# pc.net
KiCad netlist of a schematic drawn in EAGLE
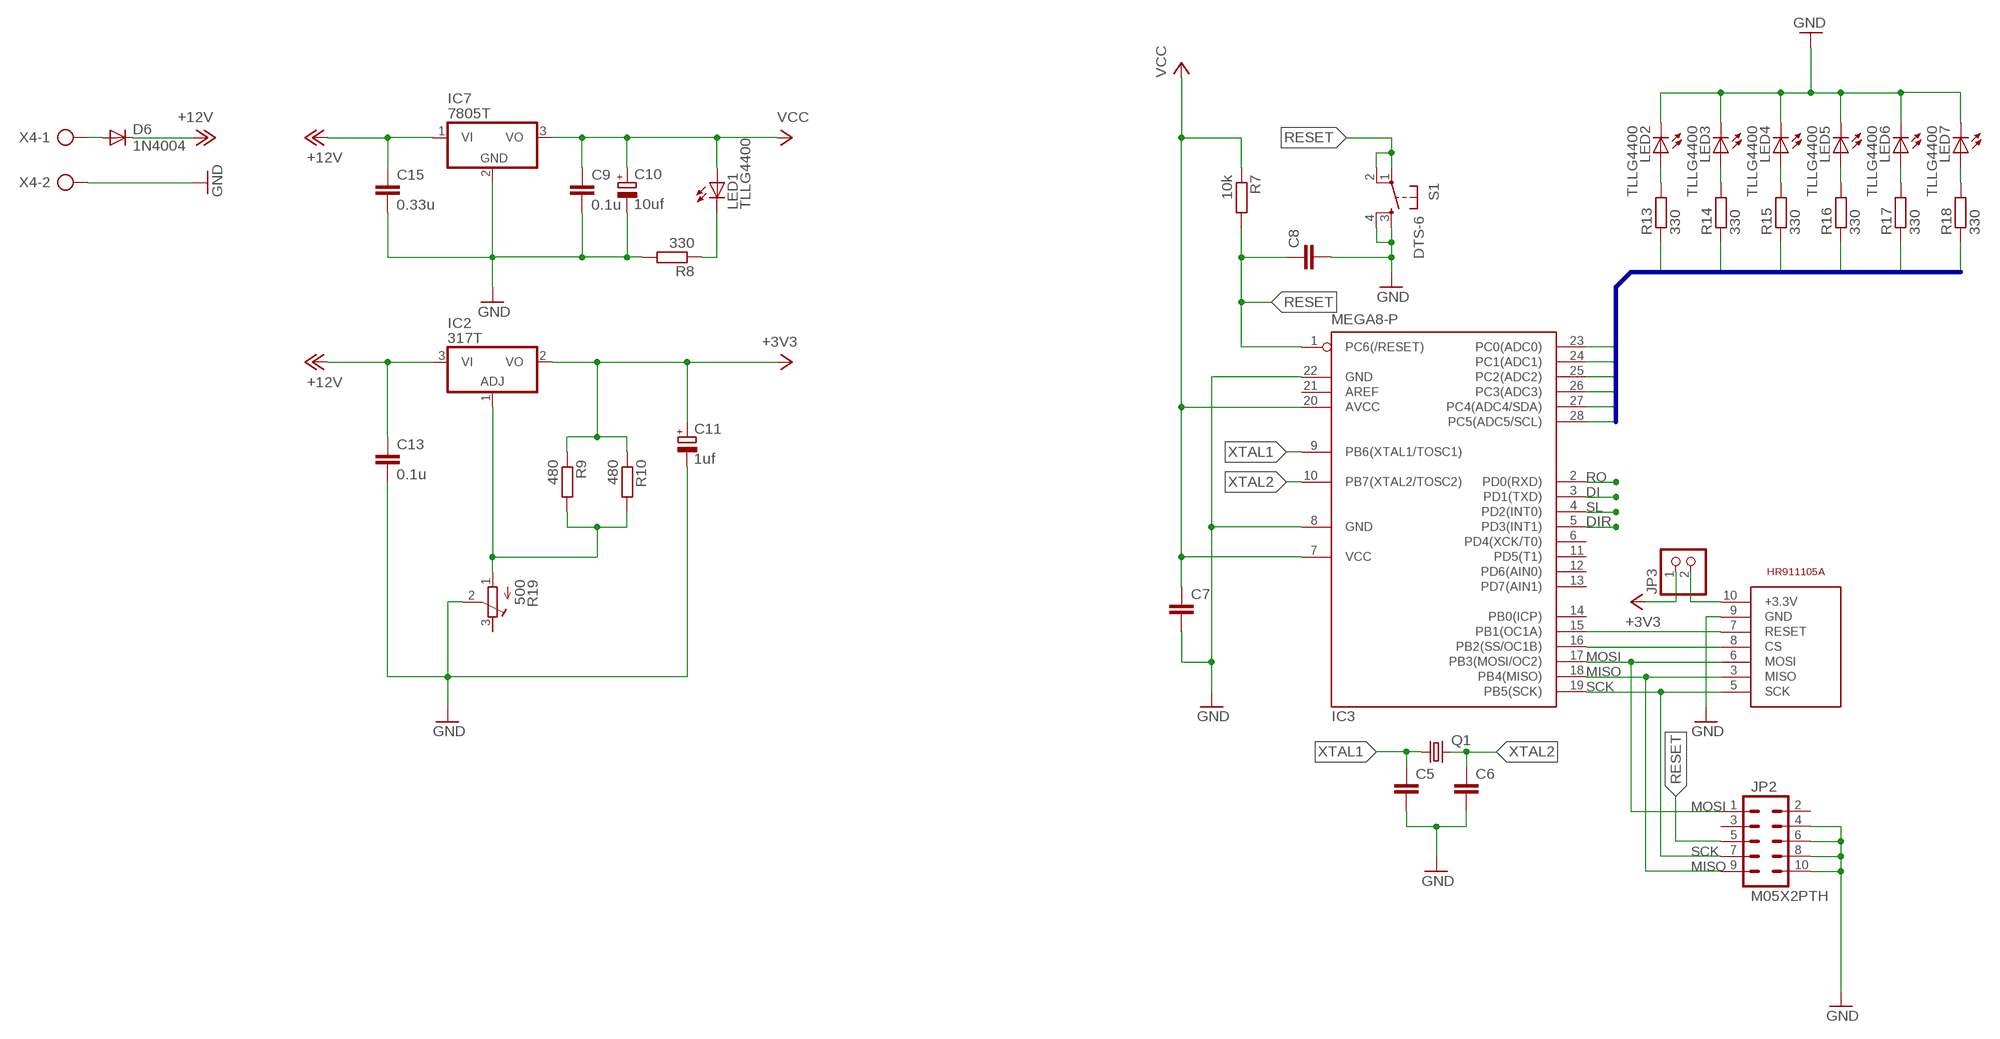
[diagram p0: schematic, sheet 1, part 1 of 2]
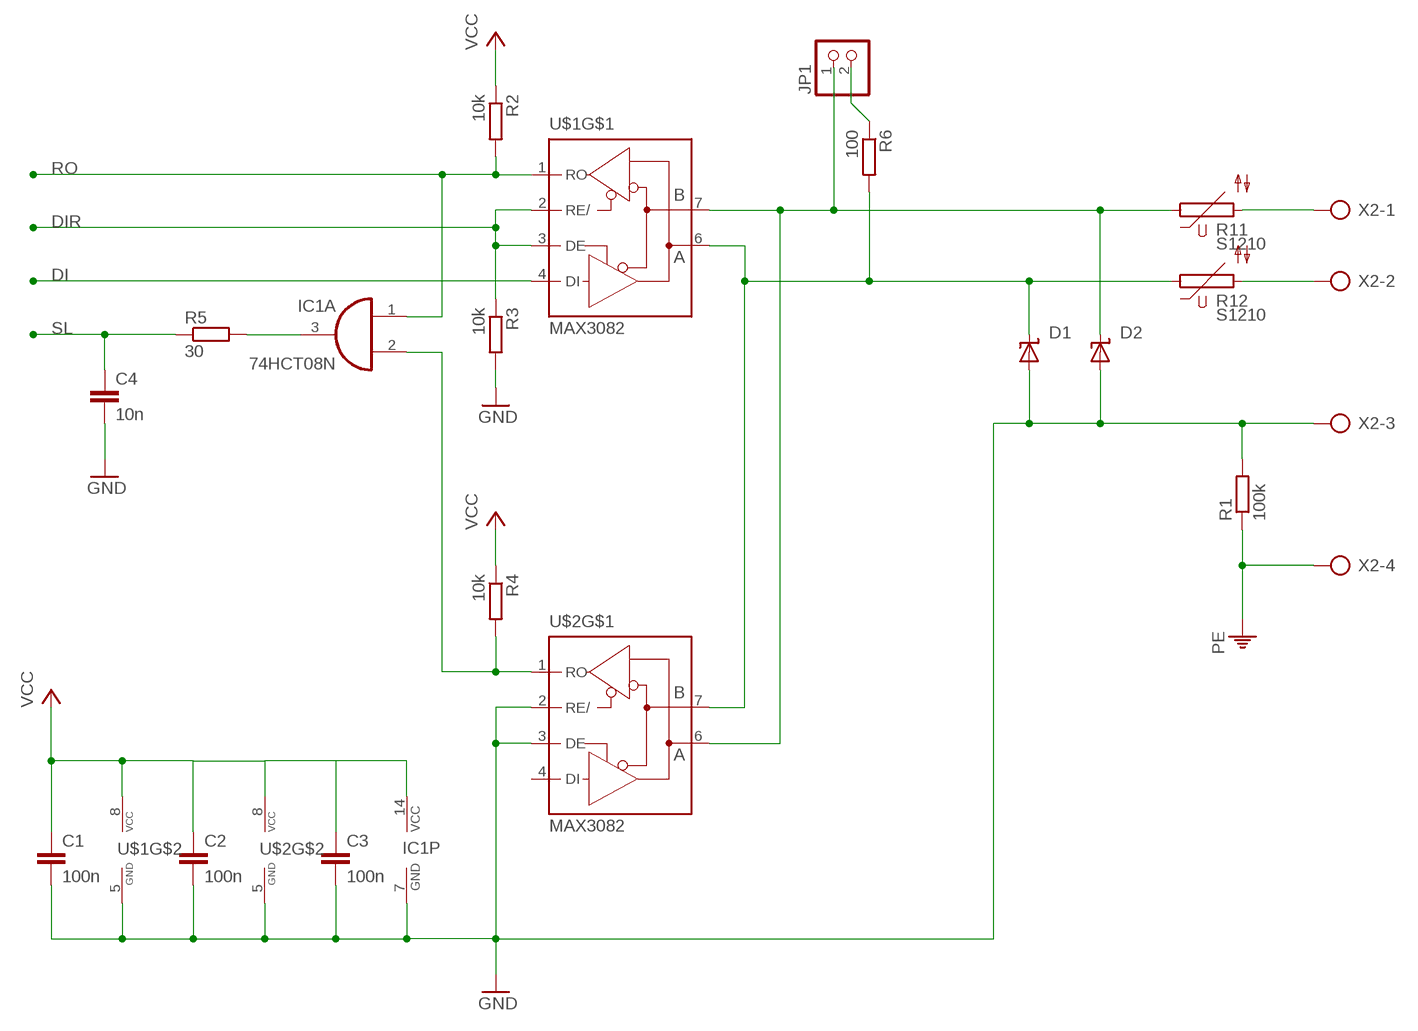
[diagram p1: schematic, sheet 1, part 2 of 2]

(export (version "E")
  (design (tool "Eeschema 10.0.6"))
  (components
    (comp (ref "C1")
      (value "100n")
      (footprint "eagle-import:C050-035X075")
      (libsource (lib "eagle-import") (part "C-EU050-035X075"))
    )
    (comp (ref "C2")
      (value "100n")
      (footprint "eagle-import:C050-035X075")
      (libsource (lib "eagle-import") (part "C-EU050-035X075"))
    )
    (comp (ref "C3")
      (value "100n")
      (footprint "eagle-import:C050-035X075")
      (libsource (lib "eagle-import") (part "C-EU050-035X075"))
    )
    (comp (ref "C4")
      (value "10n")
      (footprint "eagle-import:C050-035X075")
      (libsource (lib "eagle-import") (part "C-EU050-035X075"))
    )
    (comp (ref "C5")
      (value "C-EU050-024X044")
      (footprint "eagle-import:C050-024X044")
      (libsource (lib "eagle-import") (part "C-EU050-024X044"))
    )
    (comp (ref "C6")
      (value "C-EU050-024X044")
      (footprint "eagle-import:C050-024X044")
      (libsource (lib "eagle-import") (part "C-EU050-024X044"))
    )
    (comp (ref "C7")
      (value "C-EU050-025X075")
      (footprint "eagle-import:C050-025X075")
      (libsource (lib "eagle-import") (part "C-EU050-025X075"))
    )
    (comp (ref "C8")
      (value "C-EU050-025X075")
      (footprint "eagle-import:C050-025X075")
      (libsource (lib "eagle-import") (part "C-EU050-025X075"))
    )
    (comp (ref "C9")
      (value "0.1u")
      (footprint "eagle-import:C025-024X044")
      (libsource (lib "eagle-import") (part "C-EU025-024X044"))
    )
    (comp (ref "C10")
      (value "10uf")
      (footprint "eagle-import:E2-4")
      (libsource (lib "eagle-import") (part "CPOL-EUE2-4"))
    )
    (comp (ref "C11")
      (value "1uf")
      (footprint "eagle-import:E2-4")
      (libsource (lib "eagle-import") (part "CPOL-EUE2-4"))
    )
    (comp (ref "C13")
      (value "0.1u")
      (footprint "eagle-import:C025-024X044")
      (libsource (lib "eagle-import") (part "C-EU025-024X044"))
    )
    (comp (ref "C15")
      (value "0.33u")
      (footprint "eagle-import:C025-024X044")
      (libsource (lib "eagle-import") (part "C-EU025-024X044"))
    )
    (comp (ref "D1")
      (value "SUPPRESSOR-SMBJ")
      (footprint "eagle-import:SMBJ")
      (libsource (lib "eagle-import") (part "SUPPRESSOR-SMBJ"))
    )
    (comp (ref "D2")
      (value "SUPPRESSOR-SMBJ")
      (footprint "eagle-import:SMBJ")
      (libsource (lib "eagle-import") (part "SUPPRESSOR-SMBJ"))
    )
    (comp (ref "D6")
      (value "1N4004")
      (footprint "eagle-import:DO41-10")
      (libsource (lib "eagle-import") (part "1N4004"))
    )
    (comp (ref "IC1")
      (value "74HCT08N")
      (footprint "eagle-import:DIL14")
      (libsource (lib "eagle-import") (part "7408NHCT"))
    )
    (comp (ref "IC2")
      (value "317T")
      (footprint "eagle-import:TO220H")
      (libsource (lib "eagle-import") (part "317T"))
    )
    (comp (ref "IC3")
      (value "MEGA8-P")
      (footprint "eagle-import:DIL28-3")
      (libsource (lib "eagle-import") (part "MEGA8-P"))
    )
    (comp (ref "IC7")
      (value "7805T")
      (footprint "eagle-import:TO220H")
      (libsource (lib "eagle-import") (part "78T05"))
    )
    (comp (ref "JP1")
      (value "PINHD-1X2")
      (footprint "eagle-import:1X02")
      (libsource (lib "eagle-import") (part "PINHD-1X2"))
    )
    (comp (ref "JP2")
      (value "M05X2PTH")
      (footprint "eagle-import:AVR_ICSP")
      (libsource (lib "eagle-import") (part "M05X2PTH"))
    )
    (comp (ref "JP3")
      (value "PINHD-1X2")
      (footprint "eagle-import:1X02")
      (libsource (lib "eagle-import") (part "PINHD-1X2"))
    )
    (comp (ref "LED1")
      (value "TLLG4400")
      (footprint "eagle-import:LED3MM")
      (fields (field (name "MF") "VISHAY SEMICONDUCTOR"))
      (libsource (lib "eagle-import") (part "TLLG4400"))
    )
    (comp (ref "LED2")
      (value "TLLG4400")
      (footprint "eagle-import:LED3MM")
      (fields (field (name "MF") "VISHAY SEMICONDUCTOR"))
      (libsource (lib "eagle-import") (part "TLLG4400"))
    )
    (comp (ref "LED3")
      (value "TLLG4400")
      (footprint "eagle-import:LED3MM")
      (fields (field (name "MF") "VISHAY SEMICONDUCTOR"))
      (libsource (lib "eagle-import") (part "TLLG4400"))
    )
    (comp (ref "LED4")
      (value "TLLG4400")
      (footprint "eagle-import:LED3MM")
      (fields (field (name "MF") "VISHAY SEMICONDUCTOR"))
      (libsource (lib "eagle-import") (part "TLLG4400"))
    )
    (comp (ref "LED5")
      (value "TLLG4400")
      (footprint "eagle-import:LED3MM")
      (fields (field (name "MF") "VISHAY SEMICONDUCTOR"))
      (libsource (lib "eagle-import") (part "TLLG4400"))
    )
    (comp (ref "LED6")
      (value "TLLG4400")
      (footprint "eagle-import:LED3MM")
      (fields (field (name "MF") "VISHAY SEMICONDUCTOR"))
      (libsource (lib "eagle-import") (part "TLLG4400"))
    )
    (comp (ref "LED7")
      (value "TLLG4400")
      (footprint "eagle-import:LED3MM")
      (fields (field (name "MF") "VISHAY SEMICONDUCTOR"))
      (libsource (lib "eagle-import") (part "TLLG4400"))
    )
    (comp (ref "Q1")
      (value "CRYSTALHC49U70")
      (footprint "eagle-import:HC49U70")
      (libsource (lib "eagle-import") (part "CRYSTALHC49U70"))
    )
    (comp (ref "R1")
      (value "100k")
      (footprint "eagle-import:0204_7")
      (libsource (lib "eagle-import") (part "resistor_R-EU_0204/7"))
    )
    (comp (ref "R2")
      (value "10k")
      (footprint "eagle-import:0204_7")
      (libsource (lib "eagle-import") (part "resistor_R-EU_0204/7"))
    )
    (comp (ref "R3")
      (value "10k")
      (footprint "eagle-import:0204_7")
      (libsource (lib "eagle-import") (part "resistor_R-EU_0204/7"))
    )
    (comp (ref "R4")
      (value "10k")
      (footprint "eagle-import:0204_7")
      (libsource (lib "eagle-import") (part "resistor_R-EU_0204/7"))
    )
    (comp (ref "R5")
      (value "30")
      (footprint "eagle-import:0207_10")
      (libsource (lib "eagle-import") (part "R-EU_0207/10"))
    )
    (comp (ref "R6")
      (value "100")
      (footprint "eagle-import:0204_7")
      (libsource (lib "eagle-import") (part "resistor_R-EU_0204/7"))
    )
    (comp (ref "R7")
      (value "10k")
      (footprint "eagle-import:0204_7")
      (libsource (lib "eagle-import") (part "R-EU_0204/7"))
    )
    (comp (ref "R8")
      (value "330")
      (footprint "eagle-import:0204_7")
      (libsource (lib "eagle-import") (part "R-EU_0204/7"))
    )
    (comp (ref "R9")
      (value "480")
      (footprint "eagle-import:0204_7")
      (libsource (lib "eagle-import") (part "R-EU_0204/7"))
    )
    (comp (ref "R10")
      (value "480")
      (footprint "eagle-import:0204_7")
      (libsource (lib "eagle-import") (part "R-EU_0204/7"))
    )
    (comp (ref "R11")
      (value "S1210")
      (footprint "eagle-import:S1210")
      (libsource (lib "eagle-import") (part "S1210"))
    )
    (comp (ref "R12")
      (value "S1210")
      (footprint "eagle-import:S1210")
      (libsource (lib "eagle-import") (part "S1210"))
    )
    (comp (ref "R13")
      (value "330")
      (footprint "eagle-import:0204_7")
      (libsource (lib "eagle-import") (part "R-EU_0204/7"))
    )
    (comp (ref "R14")
      (value "330")
      (footprint "eagle-import:0204_7")
      (libsource (lib "eagle-import") (part "R-EU_0204/7"))
    )
    (comp (ref "R15")
      (value "330")
      (footprint "eagle-import:0204_7")
      (libsource (lib "eagle-import") (part "R-EU_0204/7"))
    )
    (comp (ref "R16")
      (value "330")
      (footprint "eagle-import:0204_7")
      (libsource (lib "eagle-import") (part "R-EU_0204/7"))
    )
    (comp (ref "R17")
      (value "330")
      (footprint "eagle-import:0204_7")
      (libsource (lib "eagle-import") (part "R-EU_0204/7"))
    )
    (comp (ref "R18")
      (value "330")
      (footprint "eagle-import:0204_7")
      (libsource (lib "eagle-import") (part "R-EU_0204/7"))
    )
    (comp (ref "R19")
      (value "500")
      (footprint "eagle-import:RTRIM64W")
      (libsource (lib "eagle-import") (part "R-TRIMM64W"))
    )
    (comp (ref "S1")
      (value "DTS-6")
      (footprint "eagle-import:DTS-6")
      (libsource (lib "eagle-import") (part "DTS-6"))
    )
    (comp (ref "U$1")
      (value "MAX3082")
      (footprint "eagle-import:DIL08")
      (libsource (lib "eagle-import") (part "MAX3082"))
    )
    (comp (ref "U$2")
      (value "MAX3082")
      (footprint "eagle-import:DIL08")
      (libsource (lib "eagle-import") (part "MAX3082"))
    )
    (comp (ref "U$3")
      (value "HR911105A")
      (footprint "eagle-import:HR911105A")
      (libsource (lib "eagle-import") (part "HR911105A"))
    )
    (comp (ref "X2")
      (value "AK500/4")
      (footprint "eagle-import:AK500_4")
      (libsource (lib "eagle-import") (part "AK500/4"))
    )
    (comp (ref "X4")
      (value "AK500/2-H")
      (footprint "eagle-import:AK500_2-H")
      (libsource (lib "eagle-import") (part "AK500/2-H"))
    )
  )
  (nets
    (net (code "1") (name "+3V3") (class "Default")
      (node (ref "C11") (pin "+") (pinfunction "+_+") (pintype "passive"))
      (node (ref "IC2") (pin "2") (pinfunction "VO_2") (pintype "passive"))
      (node (ref "JP3") (pin "1") (pinfunction "1_1") (pintype "passive"))
      (node (ref "R10") (pin "1") (pinfunction "1_1") (pintype "passive"))
      (node (ref "R9") (pin "1") (pinfunction "1_1") (pintype "passive"))
    )
    (net (code "2") (name "+12V") (class "Default")
      (node (ref "C13") (pin "1") (pinfunction "1_1") (pintype "passive"))
      (node (ref "C15") (pin "1") (pinfunction "1_1") (pintype "passive"))
      (node (ref "D6") (pin "C") (pinfunction "C_C") (pintype "passive"))
      (node (ref "IC2") (pin "3") (pinfunction "VI_3") (pintype "input"))
      (node (ref "IC7") (pin "1") (pinfunction "VI_1") (pintype "input"))
    )
    (net (code "3") (name "/DI") (class "Default")
      (node (ref "IC3") (pin "3") (pinfunction "PD1(TXD)_3") (pintype "bidirectional"))
      (node (ref "U$1") (pin "4") (pinfunction "DI_4") (pintype "input"))
    )
    (net (code "4") (name "/DIR") (class "Default")
      (node (ref "IC3") (pin "5") (pinfunction "PD3(INT1)_5") (pintype "bidirectional"))
      (node (ref "R3") (pin "1") (pinfunction "1_1") (pintype "passive"))
      (node (ref "U$1") (pin "2") (pinfunction "RE/_2") (pintype "input"))
      (node (ref "U$1") (pin "3") (pinfunction "DE_3") (pintype "input"))
    )
    (net (code "5") (name "/LED0") (class "Default")
      (node (ref "IC3") (pin "23") (pinfunction "PC0(ADC0)_23") (pintype "bidirectional"))
      (node (ref "R13") (pin "1") (pinfunction "1_1") (pintype "passive"))
    )
    (net (code "6") (name "/LED1") (class "Default")
      (node (ref "IC3") (pin "24") (pinfunction "PC1(ADC1)_24") (pintype "bidirectional"))
      (node (ref "R14") (pin "1") (pinfunction "1_1") (pintype "passive"))
    )
    (net (code "7") (name "/LED2") (class "Default")
      (node (ref "IC3") (pin "25") (pinfunction "PC2(ADC2)_25") (pintype "bidirectional"))
      (node (ref "R15") (pin "1") (pinfunction "1_1") (pintype "passive"))
    )
    (net (code "8") (name "/LED3") (class "Default")
      (node (ref "IC3") (pin "26") (pinfunction "PC3(ADC3)_26") (pintype "bidirectional"))
      (node (ref "R16") (pin "1") (pinfunction "1_1") (pintype "passive"))
    )
    (net (code "9") (name "/LED4") (class "Default")
      (node (ref "IC3") (pin "27") (pinfunction "PC4(ADC4/SDA)_27") (pintype "bidirectional"))
      (node (ref "R17") (pin "1") (pinfunction "1_1") (pintype "passive"))
    )
    (net (code "10") (name "/LED5") (class "Default")
      (node (ref "IC3") (pin "28") (pinfunction "PC5(ADC5/SCL)_28") (pintype "bidirectional"))
      (node (ref "R18") (pin "1") (pinfunction "1_1") (pintype "passive"))
    )
    (net (code "11") (name "/MISO") (class "Default")
      (node (ref "IC3") (pin "18") (pinfunction "PB4(MISO)_18") (pintype "bidirectional"))
      (node (ref "JP2") (pin "9") (pinfunction "9_9") (pintype "passive"))
      (node (ref "U$3") (pin "3") (pinfunction "MISO_3") (pintype "bidirectional"))
    )
    (net (code "12") (name "/MOSI") (class "Default")
      (node (ref "IC3") (pin "17") (pinfunction "PB3(MOSI/OC2)_17") (pintype "bidirectional"))
      (node (ref "JP2") (pin "1") (pinfunction "1_1") (pintype "passive"))
      (node (ref "U$3") (pin "6") (pinfunction "MOSI_6") (pintype "bidirectional"))
    )
    (net (code "13") (name "/RO") (class "Default")
      (node (ref "IC1") (pin "1") (pinfunction "I0_1") (pintype "input"))
      (node (ref "IC3") (pin "2") (pinfunction "PD0(RXD)_2") (pintype "bidirectional"))
      (node (ref "R2") (pin "2") (pinfunction "2_2") (pintype "passive"))
      (node (ref "U$1") (pin "1") (pinfunction "RO_1") (pintype "output"))
    )
    (net (code "14") (name "/SCK") (class "Default")
      (node (ref "IC3") (pin "19") (pinfunction "PB5(SCK)_19") (pintype "bidirectional"))
      (node (ref "JP2") (pin "7") (pinfunction "7_7") (pintype "passive"))
      (node (ref "U$3") (pin "5") (pinfunction "SCK_5") (pintype "bidirectional"))
    )
    (net (code "15") (name "/SL") (class "Default")
      (node (ref "C4") (pin "1") (pinfunction "1_1") (pintype "passive"))
      (node (ref "IC3") (pin "4") (pinfunction "PD2(INT0)_4") (pintype "bidirectional"))
      (node (ref "R5") (pin "1") (pinfunction "1_1") (pintype "passive"))
    )
    (net (code "16") (name "GND") (class "Default")
      (node (ref "C1") (pin "2") (pinfunction "2_2") (pintype "passive"))
      (node (ref "C10") (pin "-") (pinfunction "-_-") (pintype "passive"))
      (node (ref "C11") (pin "-") (pinfunction "-_-") (pintype "passive"))
      (node (ref "C13") (pin "2") (pinfunction "2_2") (pintype "passive"))
      (node (ref "C15") (pin "2") (pinfunction "2_2") (pintype "passive"))
      (node (ref "C2") (pin "2") (pinfunction "2_2") (pintype "passive"))
      (node (ref "C3") (pin "2") (pinfunction "2_2") (pintype "passive"))
      (node (ref "C4") (pin "2") (pinfunction "2_2") (pintype "passive"))
      (node (ref "C5") (pin "2") (pinfunction "2_2") (pintype "passive"))
      (node (ref "C6") (pin "2") (pinfunction "2_2") (pintype "passive"))
      (node (ref "C7") (pin "2") (pinfunction "2_2") (pintype "passive"))
      (node (ref "C8") (pin "2") (pinfunction "2_2") (pintype "passive"))
      (node (ref "C9") (pin "2") (pinfunction "2_2") (pintype "passive"))
      (node (ref "D1") (pin "A") (pinfunction "A_A") (pintype "passive"))
      (node (ref "D2") (pin "A") (pinfunction "A_A") (pintype "passive"))
      (node (ref "IC1") (pin "7") (pinfunction "GND_7") (pintype "power_in"))
      (node (ref "IC3") (pin "22") (pinfunction "GND_22") (pintype "power_in"))
      (node (ref "IC3") (pin "8") (pinfunction "GND_8") (pintype "power_in"))
      (node (ref "IC7") (pin "2") (pinfunction "GND_2") (pintype "passive"))
      (node (ref "JP2") (pin "10") (pinfunction "10_10") (pintype "passive"))
      (node (ref "JP2") (pin "4") (pinfunction "4_4") (pintype "passive"))
      (node (ref "JP2") (pin "6") (pinfunction "6_6") (pintype "passive"))
      (node (ref "JP2") (pin "8") (pinfunction "8_8") (pintype "passive"))
      (node (ref "LED2") (pin "K") (pinfunction "C_K") (pintype "passive"))
      (node (ref "LED3") (pin "K") (pinfunction "C_K") (pintype "passive"))
      (node (ref "LED4") (pin "K") (pinfunction "C_K") (pintype "passive"))
      (node (ref "LED5") (pin "K") (pinfunction "C_K") (pintype "passive"))
      (node (ref "LED6") (pin "K") (pinfunction "C_K") (pintype "passive"))
      (node (ref "LED7") (pin "K") (pinfunction "C_K") (pintype "passive"))
      (node (ref "R1") (pin "2") (pinfunction "2_2") (pintype "passive"))
      (node (ref "R19") (pin "2") (pinfunction "S_2") (pintype "passive"))
      (node (ref "R3") (pin "2") (pinfunction "2_2") (pintype "passive"))
      (node (ref "R8") (pin "2") (pinfunction "2_2") (pintype "passive"))
      (node (ref "S1") (pin "3") (pinfunction "3_3") (pintype "passive"))
      (node (ref "S1") (pin "4") (pinfunction "4_4") (pintype "passive"))
      (node (ref "U$1") (pin "5") (pinfunction "GND_5") (pintype "power_in"))
      (node (ref "U$2") (pin "2") (pinfunction "RE/_2") (pintype "input"))
      (node (ref "U$2") (pin "3") (pinfunction "DE_3") (pintype "input"))
      (node (ref "U$2") (pin "5") (pinfunction "GND_5") (pintype "power_in"))
      (node (ref "U$3") (pin "9") (pinfunction "GND_9") (pintype "bidirectional"))
      (node (ref "X2") (pin "3") (pinfunction "KL_3") (pintype "passive"))
      (node (ref "X4") (pin "2") (pinfunction "KL_2") (pintype "passive"))
    )
    (net (code "17") (name "Net-(IC1A-I1)") (class "Default")
      (node (ref "IC1") (pin "2") (pinfunction "I1_2") (pintype "input"))
      (node (ref "R4") (pin "2") (pinfunction "2_2") (pintype "passive"))
      (node (ref "U$2") (pin "1") (pinfunction "RO_1") (pintype "output"))
    )
    (net (code "18") (name "Net-(IC1A-O)") (class "Default")
      (node (ref "IC1") (pin "3") (pinfunction "O_3") (pintype "output"))
      (node (ref "R5") (pin "2") (pinfunction "2_2") (pintype "passive"))
    )
    (net (code "19") (name "Net-(IC2-ADJ)") (class "Default")
      (node (ref "IC2") (pin "1") (pinfunction "ADJ_1") (pintype "input"))
      (node (ref "R10") (pin "2") (pinfunction "2_2") (pintype "passive"))
      (node (ref "R19") (pin "1") (pinfunction "A_1") (pintype "passive"))
      (node (ref "R9") (pin "2") (pinfunction "2_2") (pintype "passive"))
    )
    (net (code "20") (name "Net-(IC3-PB1(OC1A))") (class "Default")
      (node (ref "IC3") (pin "15") (pinfunction "PB1(OC1A)_15") (pintype "bidirectional"))
      (node (ref "U$3") (pin "7") (pinfunction "RESET_7") (pintype "bidirectional"))
    )
    (net (code "21") (name "Net-(IC3-PB2(SS{slash}OC1B))") (class "Default")
      (node (ref "IC3") (pin "16") (pinfunction "PB2(SS/OC1B)_16") (pintype "bidirectional"))
      (node (ref "U$3") (pin "8") (pinfunction "CS_8") (pintype "bidirectional"))
    )
    (net (code "22") (name "Net-(JP1-Pad2)") (class "Default")
      (node (ref "JP1") (pin "2") (pinfunction "2_2") (pintype "passive"))
      (node (ref "R6") (pin "1") (pinfunction "1_1") (pintype "passive"))
    )
    (net (code "23") (name "Net-(LED1-C)") (class "Default")
      (node (ref "LED1") (pin "K") (pinfunction "C_K") (pintype "passive"))
      (node (ref "R8") (pin "1") (pinfunction "1_1") (pintype "passive"))
    )
    (net (code "24") (name "Net-(LED2-PadA)") (class "Default")
      (node (ref "LED2") (pin "A") (pinfunction "A_A") (pintype "passive"))
      (node (ref "R13") (pin "2") (pinfunction "2_2") (pintype "passive"))
    )
    (net (code "25") (name "Net-(LED3-PadA)") (class "Default")
      (node (ref "LED3") (pin "A") (pinfunction "A_A") (pintype "passive"))
      (node (ref "R14") (pin "2") (pinfunction "2_2") (pintype "passive"))
    )
    (net (code "26") (name "Net-(LED4-PadA)") (class "Default")
      (node (ref "LED4") (pin "A") (pinfunction "A_A") (pintype "passive"))
      (node (ref "R15") (pin "2") (pinfunction "2_2") (pintype "passive"))
    )
    (net (code "27") (name "Net-(LED5-PadA)") (class "Default")
      (node (ref "LED5") (pin "A") (pinfunction "A_A") (pintype "passive"))
      (node (ref "R16") (pin "2") (pinfunction "2_2") (pintype "passive"))
    )
    (net (code "28") (name "Net-(LED6-PadA)") (class "Default")
      (node (ref "LED6") (pin "A") (pinfunction "A_A") (pintype "passive"))
      (node (ref "R17") (pin "2") (pinfunction "2_2") (pintype "passive"))
    )
    (net (code "29") (name "Net-(LED7-PadA)") (class "Default")
      (node (ref "LED7") (pin "A") (pinfunction "A_A") (pintype "passive"))
      (node (ref "R18") (pin "2") (pinfunction "2_2") (pintype "passive"))
    )
    (net (code "30") (name "Net-(U$1A-A)") (class "Default")
      (node (ref "D1") (pin "C") (pinfunction "C_C") (pintype "passive"))
      (node (ref "R12") (pin "1") (pinfunction "1_1") (pintype "passive"))
      (node (ref "R6") (pin "2") (pinfunction "2_2") (pintype "passive"))
      (node (ref "U$1") (pin "6") (pinfunction "A_6") (pintype "passive"))
      (node (ref "U$2") (pin "7") (pinfunction "B_7") (pintype "passive"))
    )
    (net (code "31") (name "Net-(U$1A-B)") (class "Default")
      (node (ref "D2") (pin "C") (pinfunction "C_C") (pintype "passive"))
      (node (ref "JP1") (pin "1") (pinfunction "1_1") (pintype "passive"))
      (node (ref "R11") (pin "1") (pinfunction "1_1") (pintype "passive"))
      (node (ref "U$1") (pin "7") (pinfunction "B_7") (pintype "passive"))
      (node (ref "U$2") (pin "6") (pinfunction "A_6") (pintype "passive"))
    )
    (net (code "32") (name "Net-(U$3-+3.3V)") (class "Default")
      (node (ref "JP3") (pin "2") (pinfunction "2_2") (pintype "passive"))
      (node (ref "U$3") (pin "10") (pinfunction "+3.3V_10") (pintype "bidirectional"))
    )
    (net (code "33") (name "Net-(X2A-KL)") (class "Default")
      (node (ref "R11") (pin "2") (pinfunction "2_2") (pintype "passive"))
      (node (ref "X2") (pin "1") (pinfunction "KL_1") (pintype "passive"))
    )
    (net (code "34") (name "Net-(X2B-KL)") (class "Default")
      (node (ref "R12") (pin "2") (pinfunction "2_2") (pintype "passive"))
      (node (ref "X2") (pin "2") (pinfunction "KL_2") (pintype "passive"))
    )
    (net (code "35") (name "Net-(X4A-KL)") (class "Default")
      (node (ref "D6") (pin "A") (pinfunction "A_A") (pintype "passive"))
      (node (ref "X4") (pin "1") (pinfunction "KL_1") (pintype "passive"))
    )
    (net (code "36") (name "PE") (class "Default")
      (node (ref "R1") (pin "1") (pinfunction "1_1") (pintype "passive"))
      (node (ref "X2") (pin "4") (pinfunction "KL_4") (pintype "passive"))
    )
    (net (code "37") (name "RESET") (class "Default")
      (node (ref "C8") (pin "1") (pinfunction "1_1") (pintype "passive"))
      (node (ref "IC3") (pin "1") (pinfunction "PC6(/RESET)_1") (pintype "bidirectional"))
      (node (ref "JP2") (pin "5") (pinfunction "5_5") (pintype "passive"))
      (node (ref "R7") (pin "2") (pinfunction "2_2") (pintype "passive"))
      (node (ref "S1") (pin "1") (pinfunction "1_1") (pintype "passive"))
      (node (ref "S1") (pin "2") (pinfunction "2_2") (pintype "passive"))
    )
    (net (code "38") (name "VCC") (class "Default")
      (node (ref "C1") (pin "1") (pinfunction "1_1") (pintype "passive"))
      (node (ref "C10") (pin "+") (pinfunction "+_+") (pintype "passive"))
      (node (ref "C2") (pin "1") (pinfunction "1_1") (pintype "passive"))
      (node (ref "C3") (pin "1") (pinfunction "1_1") (pintype "passive"))
      (node (ref "C7") (pin "1") (pinfunction "1_1") (pintype "passive"))
      (node (ref "C9") (pin "1") (pinfunction "1_1") (pintype "passive"))
      (node (ref "IC1") (pin "14") (pinfunction "VCC_14") (pintype "power_in"))
      (node (ref "IC3") (pin "20") (pinfunction "AVCC_20") (pintype "power_in"))
      (node (ref "IC3") (pin "7") (pinfunction "VCC_7") (pintype "power_in"))
      (node (ref "IC7") (pin "3") (pinfunction "VO_3") (pintype "passive"))
      (node (ref "LED1") (pin "A") (pinfunction "A_A") (pintype "passive"))
      (node (ref "R2") (pin "1") (pinfunction "1_1") (pintype "passive"))
      (node (ref "R4") (pin "1") (pinfunction "1_1") (pintype "passive"))
      (node (ref "R7") (pin "1") (pinfunction "1_1") (pintype "passive"))
      (node (ref "U$1") (pin "8") (pinfunction "VCC_8") (pintype "power_in"))
      (node (ref "U$2") (pin "8") (pinfunction "VCC_8") (pintype "power_in"))
    )
    (net (code "39") (name "XTAL1") (class "Default")
      (node (ref "C5") (pin "1") (pinfunction "1_1") (pintype "passive"))
      (node (ref "IC3") (pin "9") (pinfunction "PB6(XTAL1/TOSC1)_9") (pintype "bidirectional"))
      (node (ref "Q1") (pin "1") (pinfunction "1_1") (pintype "passive"))
    )
    (net (code "40") (name "XTAL2") (class "Default")
      (node (ref "C6") (pin "1") (pinfunction "1_1") (pintype "passive"))
      (node (ref "IC3") (pin "10") (pinfunction "PB7(XTAL2/TOSC2)_10") (pintype "bidirectional"))
      (node (ref "Q1") (pin "2") (pinfunction "2_2") (pintype "passive"))
    )
    (net (code "41") (name "unconnected-(IC3-AREF-Pad21)") (class "Default")
      (node (ref "IC3") (pin "21") (pinfunction "AREF_21") (pintype "passive"))
    )
    (net (code "42") (name "unconnected-(IC3-PB0(ICP)-Pad14)") (class "Default")
      (node (ref "IC3") (pin "14") (pinfunction "PB0(ICP)_14") (pintype "bidirectional"))
    )
    (net (code "43") (name "unconnected-(IC3-PD4(XCK{slash}T0)-Pad6)") (class "Default")
      (node (ref "IC3") (pin "6") (pinfunction "PD4(XCK/T0)_6") (pintype "bidirectional"))
    )
    (net (code "44") (name "unconnected-(IC3-PD5(T1)-Pad11)") (class "Default")
      (node (ref "IC3") (pin "11") (pinfunction "PD5(T1)_11") (pintype "bidirectional"))
    )
    (net (code "45") (name "unconnected-(IC3-PD6(AIN0)-Pad12)") (class "Default")
      (node (ref "IC3") (pin "12") (pinfunction "PD6(AIN0)_12") (pintype "bidirectional"))
    )
    (net (code "46") (name "unconnected-(IC3-PD7(AIN1)-Pad13)") (class "Default")
      (node (ref "IC3") (pin "13") (pinfunction "PD7(AIN1)_13") (pintype "bidirectional"))
    )
    (net (code "47") (name "unconnected-(JP2-Pad2)") (class "Default")
      (node (ref "JP2") (pin "2") (pinfunction "2_2") (pintype "passive"))
    )
    (net (code "48") (name "unconnected-(JP2-Pad3)") (class "Default")
      (node (ref "JP2") (pin "3") (pinfunction "3_3") (pintype "passive"))
    )
    (net (code "49") (name "unconnected-(R19-E-Pad3)") (class "Default")
      (node (ref "R19") (pin "3") (pinfunction "E_3") (pintype "passive"))
    )
    (net (code "50") (name "unconnected-(U$2A-DI-Pad4)") (class "Default")
      (node (ref "U$2") (pin "4") (pinfunction "DI_4") (pintype "input"))
    )
  )
)
